# Homework_1_by_Jonathan_Pilling.net
KiCad netlist of a schematic drawn in EAGLE
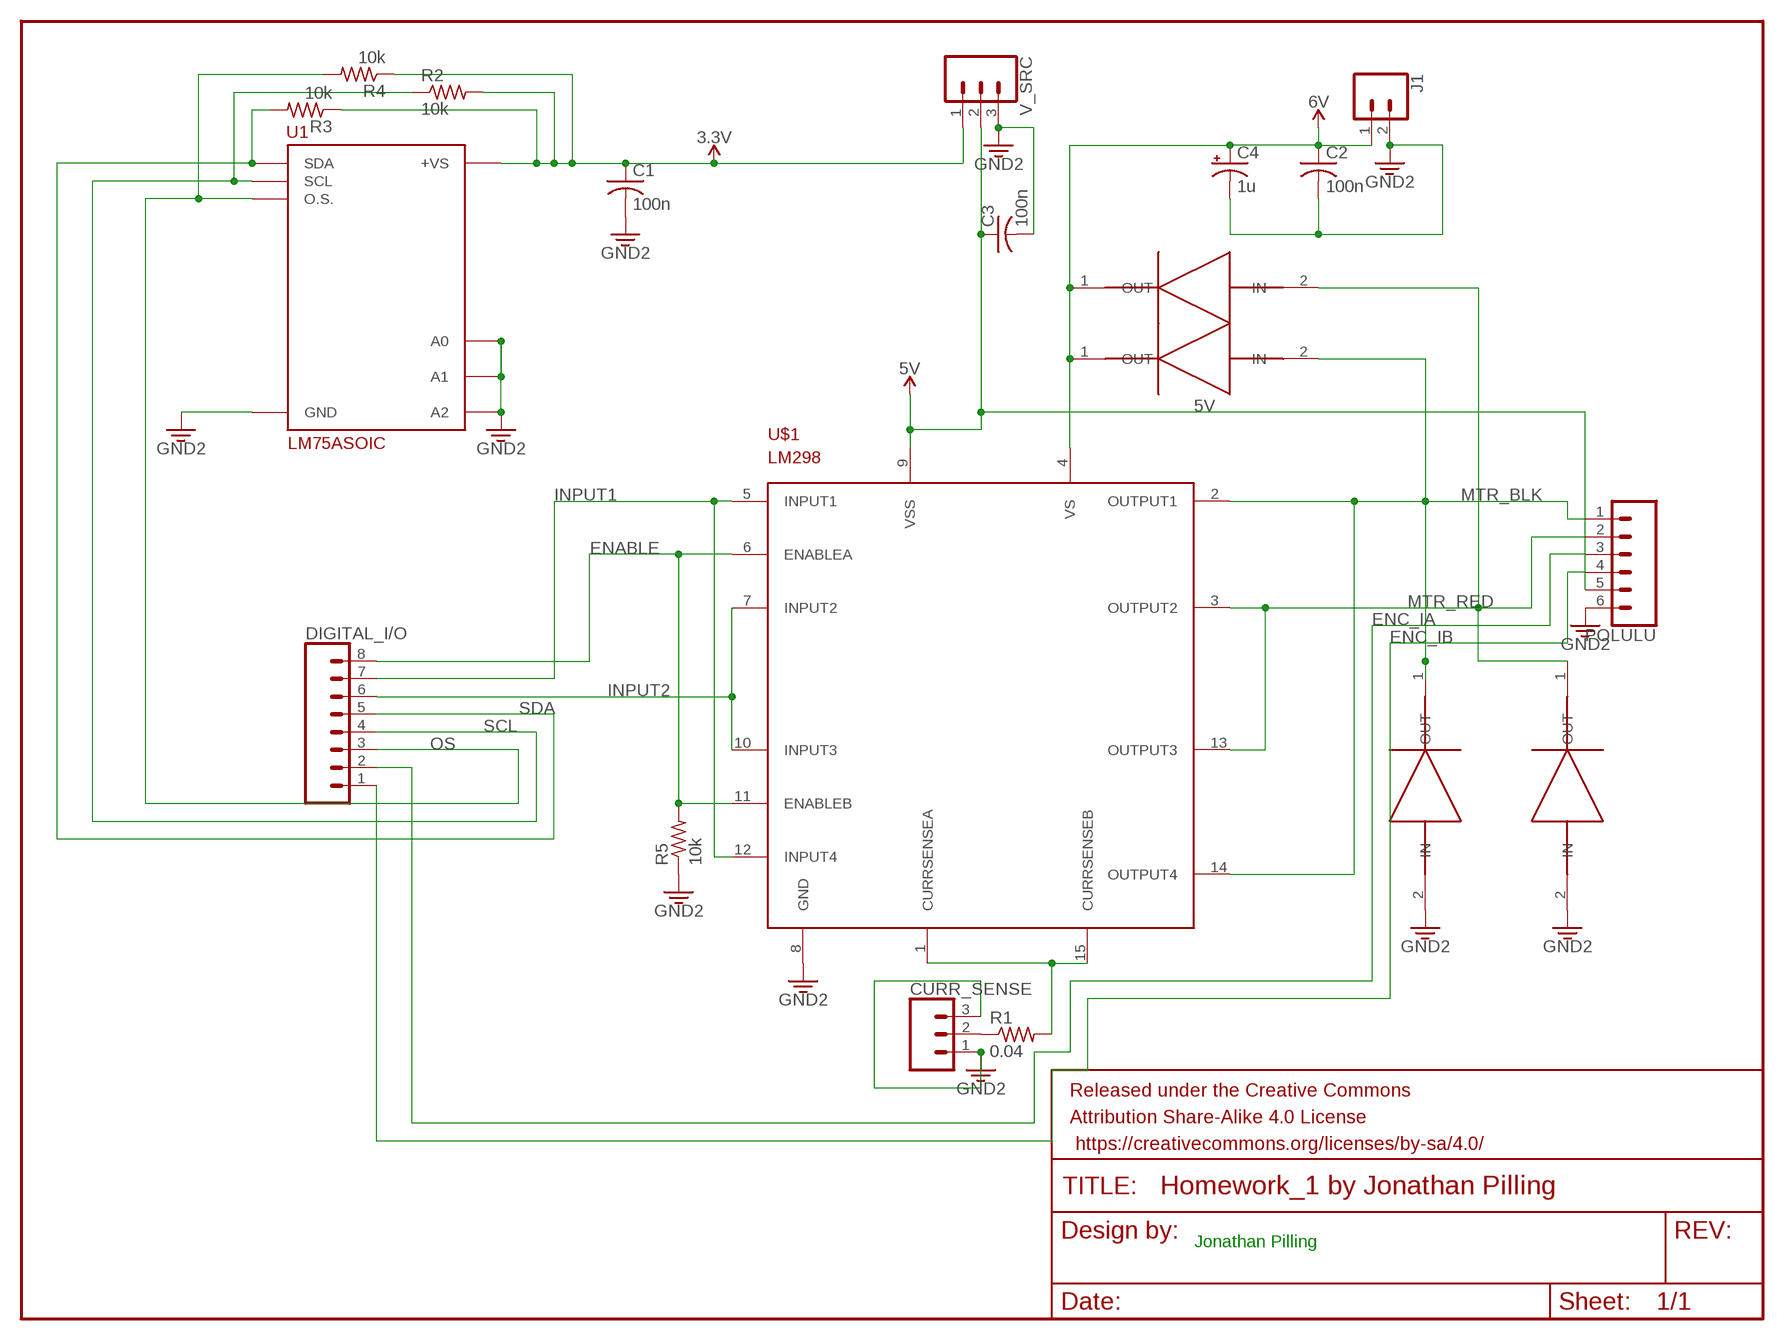
[diagram p0: schematic, sheet 1]

(export (version "E")
  (design (tool "Eeschema 10.0.6"))
  (components
    (comp (ref "C1")
      (value "100n")
      (footprint "eagle-import:C1206")
      (libsource (lib "eagle-import") (part "C-USC1206"))
    )
    (comp (ref "C2")
      (value "100n")
      (footprint "eagle-import:C1206")
      (libsource (lib "eagle-import") (part "C-USC1206"))
    )
    (comp (ref "C3")
      (value "100n")
      (footprint "eagle-import:C1206")
      (libsource (lib "eagle-import") (part "C-USC1206"))
    )
    (comp (ref "C4")
      (value "1u")
      (footprint "eagle-import:E2,5-5")
      (libsource (lib "eagle-import") (part "CPOL-USE2.5-5"))
    )
    (comp (ref "CURR_SENSE")
      (value "CONN_03")
      (footprint "eagle-import:1X03")
      (libsource (lib "eagle-import") (part "CONN_03"))
    )
    (comp (ref "D2")
      (value "SURFACE_MOUNT_DIODE")
      (footprint "eagle-import:SURFACE_MOUNT_DIODE")
      (libsource (lib "eagle-import") (part "SURFACE_MOUNT_DIODE"))
    )
    (comp (ref "DIGITAL_I/O")
      (value "CONN_08\"")
      (footprint "eagle-import:1X08")
      (libsource (lib "eagle-import") (part "CONN_08{dblquote}"))
    )
    (comp (ref "J1")
      (value "CONN_025MM")
      (footprint "eagle-import:SCREWTERMINAL-5MM-2")
      (libsource (lib "eagle-import") (part "CONN_025MM"))
    )
    (comp (ref "JONATHAN_PILLING")
      (value "Frame")
      (footprint "eagle-import:DUMMY")
      (fields (field (name "DESIGNER") "Jonathan Pilling"))
      (libsource (lib "eagle-import") (part "FRAME-LETTERNO_PACKAGE"))
    )
    (comp (ref "POLULU")
      (value "CONN_06SILK_FEMALE_PTH")
      (footprint "eagle-import:1X06")
      (libsource (lib "eagle-import") (part "CONN_06SILK_FEMALE_PTH"))
    )
    (comp (ref "R1")
      (value "0.04")
      (footprint "eagle-import:M1206")
      (libsource (lib "eagle-import") (part "R-US_M1206"))
    )
    (comp (ref "R2")
      (value "10k")
      (footprint "eagle-import:M1206")
      (libsource (lib "eagle-import") (part "R-US_M1206"))
    )
    (comp (ref "R3")
      (value "10k")
      (footprint "eagle-import:R1206")
      (libsource (lib "eagle-import") (part "R-US_R1206"))
    )
    (comp (ref "R4")
      (value "10k")
      (footprint "eagle-import:R1206")
      (libsource (lib "eagle-import") (part "R-US_R1206"))
    )
    (comp (ref "R5")
      (value "10k")
      (footprint "eagle-import:M1206")
      (libsource (lib "eagle-import") (part "R-US_M1206"))
    )
    (comp (ref "U$1")
      (value "LM298")
      (footprint "eagle-import:LM298")
      (libsource (lib "eagle-import") (part "LM298"))
    )
    (comp (ref "U$2")
      (value "SURFACE_MOUNT_DIODE")
      (footprint "eagle-import:SURFACE_MOUNT_DIODE")
      (libsource (lib "eagle-import") (part "SURFACE_MOUNT_DIODE"))
    )
    (comp (ref "U$4")
      (value "SURFACE_MOUNT_DIODE")
      (footprint "eagle-import:SURFACE_MOUNT_DIODE")
      (libsource (lib "eagle-import") (part "SURFACE_MOUNT_DIODE"))
    )
    (comp (ref "U$5")
      (value "SURFACE_MOUNT_DIODE")
      (footprint "eagle-import:SURFACE_MOUNT_DIODE")
      (libsource (lib "eagle-import") (part "SURFACE_MOUNT_DIODE"))
    )
    (comp (ref "U1")
      (value "LM75ASOIC")
      (footprint "eagle-import:LM75A")
      (libsource (lib "eagle-import") (part "LM75ASOIC"))
    )
    (comp (ref "V_SRC")
      (value "CONN_03")
      (footprint "eagle-import:1X03")
      (libsource (lib "eagle-import") (part "CONN_03"))
    )
  )
  (nets
    (net (code "1") (name "/ENABLE") (class "Default")
      (node (ref "DIGITAL_I/O") (pin "8") (pinfunction "8_8") (pintype "passive"))
      (node (ref "R5") (pin "2") (pinfunction "2_2") (pintype "passive"))
      (node (ref "U$1") (pin "11") (pinfunction "ENABLEB_11") (pintype "bidirectional"))
      (node (ref "U$1") (pin "6") (pinfunction "ENABLEA_6") (pintype "bidirectional"))
    )
    (net (code "2") (name "/ENC_IA") (class "Default")
      (node (ref "DIGITAL_I/O") (pin "2") (pinfunction "2_2") (pintype "passive"))
      (node (ref "POLULU") (pin "3") (pinfunction "3_3") (pintype "passive"))
    )
    (net (code "3") (name "/ENC_IB") (class "Default")
      (node (ref "DIGITAL_I/O") (pin "1") (pinfunction "1_1") (pintype "passive"))
      (node (ref "POLULU") (pin "4") (pinfunction "4_4") (pintype "passive"))
    )
    (net (code "4") (name "/INPUT1") (class "Default")
      (node (ref "DIGITAL_I/O") (pin "7") (pinfunction "7_7") (pintype "passive"))
      (node (ref "U$1") (pin "12") (pinfunction "INPUT4_12") (pintype "bidirectional"))
      (node (ref "U$1") (pin "5") (pinfunction "INPUT1_5") (pintype "bidirectional"))
    )
    (net (code "5") (name "/INPUT2") (class "Default")
      (node (ref "DIGITAL_I/O") (pin "6") (pinfunction "6_6") (pintype "passive"))
      (node (ref "U$1") (pin "10") (pinfunction "INPUT3_10") (pintype "input"))
      (node (ref "U$1") (pin "7") (pinfunction "INPUT2_7") (pintype "bidirectional"))
    )
    (net (code "6") (name "/MTR_BLK") (class "Default")
      (node (ref "D2") (pin "1") (pinfunction "OUT_1") (pintype "bidirectional"))
      (node (ref "POLULU") (pin "1") (pinfunction "1_1") (pintype "passive"))
      (node (ref "U$1") (pin "14") (pinfunction "OUTPUT4_14") (pintype "bidirectional"))
      (node (ref "U$1") (pin "2") (pinfunction "OUTPUT1_2") (pintype "bidirectional"))
      (node (ref "U$5") (pin "2") (pinfunction "IN_2") (pintype "bidirectional"))
    )
    (net (code "7") (name "/MTR_RED") (class "Default")
      (node (ref "POLULU") (pin "2") (pinfunction "2_2") (pintype "passive"))
      (node (ref "U$1") (pin "13") (pinfunction "OUTPUT3_13") (pintype "bidirectional"))
      (node (ref "U$1") (pin "3") (pinfunction "OUTPUT2_3") (pintype "output"))
      (node (ref "U$2") (pin "1") (pinfunction "OUT_1") (pintype "bidirectional"))
      (node (ref "U$4") (pin "2") (pinfunction "IN_2") (pintype "bidirectional"))
    )
    (net (code "8") (name "/OS") (class "Default")
      (node (ref "DIGITAL_I/O") (pin "3") (pinfunction "3_3") (pintype "passive"))
      (node (ref "R4") (pin "2") (pinfunction "2_2") (pintype "passive"))
      (node (ref "U1") (pin "3") (pinfunction "O.S._3") (pintype "bidirectional"))
    )
    (net (code "9") (name "/SCL") (class "Default")
      (node (ref "DIGITAL_I/O") (pin "4") (pinfunction "4_4") (pintype "passive"))
      (node (ref "R2") (pin "1") (pinfunction "1_1") (pintype "passive"))
      (node (ref "U1") (pin "2") (pinfunction "SCL_2") (pintype "bidirectional"))
    )
    (net (code "10") (name "/SDA") (class "Default")
      (node (ref "DIGITAL_I/O") (pin "5") (pinfunction "5_5") (pintype "passive"))
      (node (ref "R3") (pin "2") (pinfunction "2_2") (pintype "passive"))
      (node (ref "U1") (pin "1") (pinfunction "SDA_1") (pintype "bidirectional"))
    )
    (net (code "11") (name "3.3V") (class "Default")
      (node (ref "C1") (pin "1") (pinfunction "1_1") (pintype "passive"))
      (node (ref "C1") (pin "2") (pinfunction "2_2") (pintype "passive"))
      (node (ref "C2") (pin "2") (pinfunction "2_2") (pintype "passive"))
      (node (ref "C3") (pin "2") (pinfunction "2_2") (pintype "passive"))
      (node (ref "C4") (pin "-") (pinfunction "-_-") (pintype "passive"))
      (node (ref "CURR_SENSE") (pin "1") (pinfunction "1_1") (pintype "passive"))
      (node (ref "CURR_SENSE") (pin "3") (pinfunction "3_3") (pintype "passive"))
      (node (ref "D2") (pin "2") (pinfunction "IN_2") (pintype "bidirectional"))
      (node (ref "J1") (pin "2") (pinfunction "2_2") (pintype "passive"))
      (node (ref "POLULU") (pin "6") (pinfunction "6_6") (pintype "passive"))
      (node (ref "R2") (pin "2") (pinfunction "2_2") (pintype "passive"))
      (node (ref "R3") (pin "1") (pinfunction "1_1") (pintype "passive"))
      (node (ref "R4") (pin "1") (pinfunction "1_1") (pintype "passive"))
      (node (ref "R5") (pin "1") (pinfunction "1_1") (pintype "passive"))
      (node (ref "U$1") (pin "8") (pinfunction "GND_8") (pintype "power_in"))
      (node (ref "U$2") (pin "2") (pinfunction "IN_2") (pintype "bidirectional"))
      (node (ref "U1") (pin "4") (pinfunction "GND_4") (pintype "bidirectional"))
      (node (ref "U1") (pin "5") (pinfunction "A2_5") (pintype "bidirectional"))
      (node (ref "U1") (pin "6") (pinfunction "A1_6") (pintype "bidirectional"))
      (node (ref "U1") (pin "7") (pinfunction "A0_7") (pintype "bidirectional"))
      (node (ref "U1") (pin "8") (pinfunction "+VS_8") (pintype "bidirectional"))
      (node (ref "V_SRC") (pin "1") (pinfunction "1_1") (pintype "passive"))
      (node (ref "V_SRC") (pin "3") (pinfunction "3_3") (pintype "passive"))
    )
    (net (code "12") (name "5V") (class "Default")
      (node (ref "C3") (pin "1") (pinfunction "1_1") (pintype "passive"))
      (node (ref "POLULU") (pin "5") (pinfunction "5_5") (pintype "passive"))
      (node (ref "U$1") (pin "9") (pinfunction "VSS_9") (pintype "power_in"))
      (node (ref "V_SRC") (pin "2") (pinfunction "2_2") (pintype "passive"))
    )
    (net (code "13") (name "6V") (class "Default")
      (node (ref "C2") (pin "1") (pinfunction "1_1") (pintype "passive"))
      (node (ref "C4") (pin "+") (pinfunction "+_+") (pintype "passive"))
      (node (ref "J1") (pin "1") (pinfunction "1_1") (pintype "passive"))
      (node (ref "U$1") (pin "4") (pinfunction "VS_4") (pintype "power_in"))
      (node (ref "U$4") (pin "1") (pinfunction "OUT_1") (pintype "bidirectional"))
      (node (ref "U$5") (pin "1") (pinfunction "OUT_1") (pintype "bidirectional"))
    )
    (net (code "14") (name "Net-(CURR_SENSE-Pad2)") (class "Default")
      (node (ref "CURR_SENSE") (pin "2") (pinfunction "2_2") (pintype "passive"))
      (node (ref "R1") (pin "1") (pinfunction "1_1") (pintype "passive"))
    )
    (net (code "15") (name "Net-(U$1-CURRSENSEA)") (class "Default")
      (node (ref "R1") (pin "2") (pinfunction "2_2") (pintype "passive"))
      (node (ref "U$1") (pin "1") (pinfunction "CURRSENSEA_1") (pintype "bidirectional"))
      (node (ref "U$1") (pin "15") (pinfunction "CURRSENSEB_15") (pintype "bidirectional"))
    )
  )
)
